# FanControl_1-0.net
KiCad netlist of a schematic drawn in EAGLE
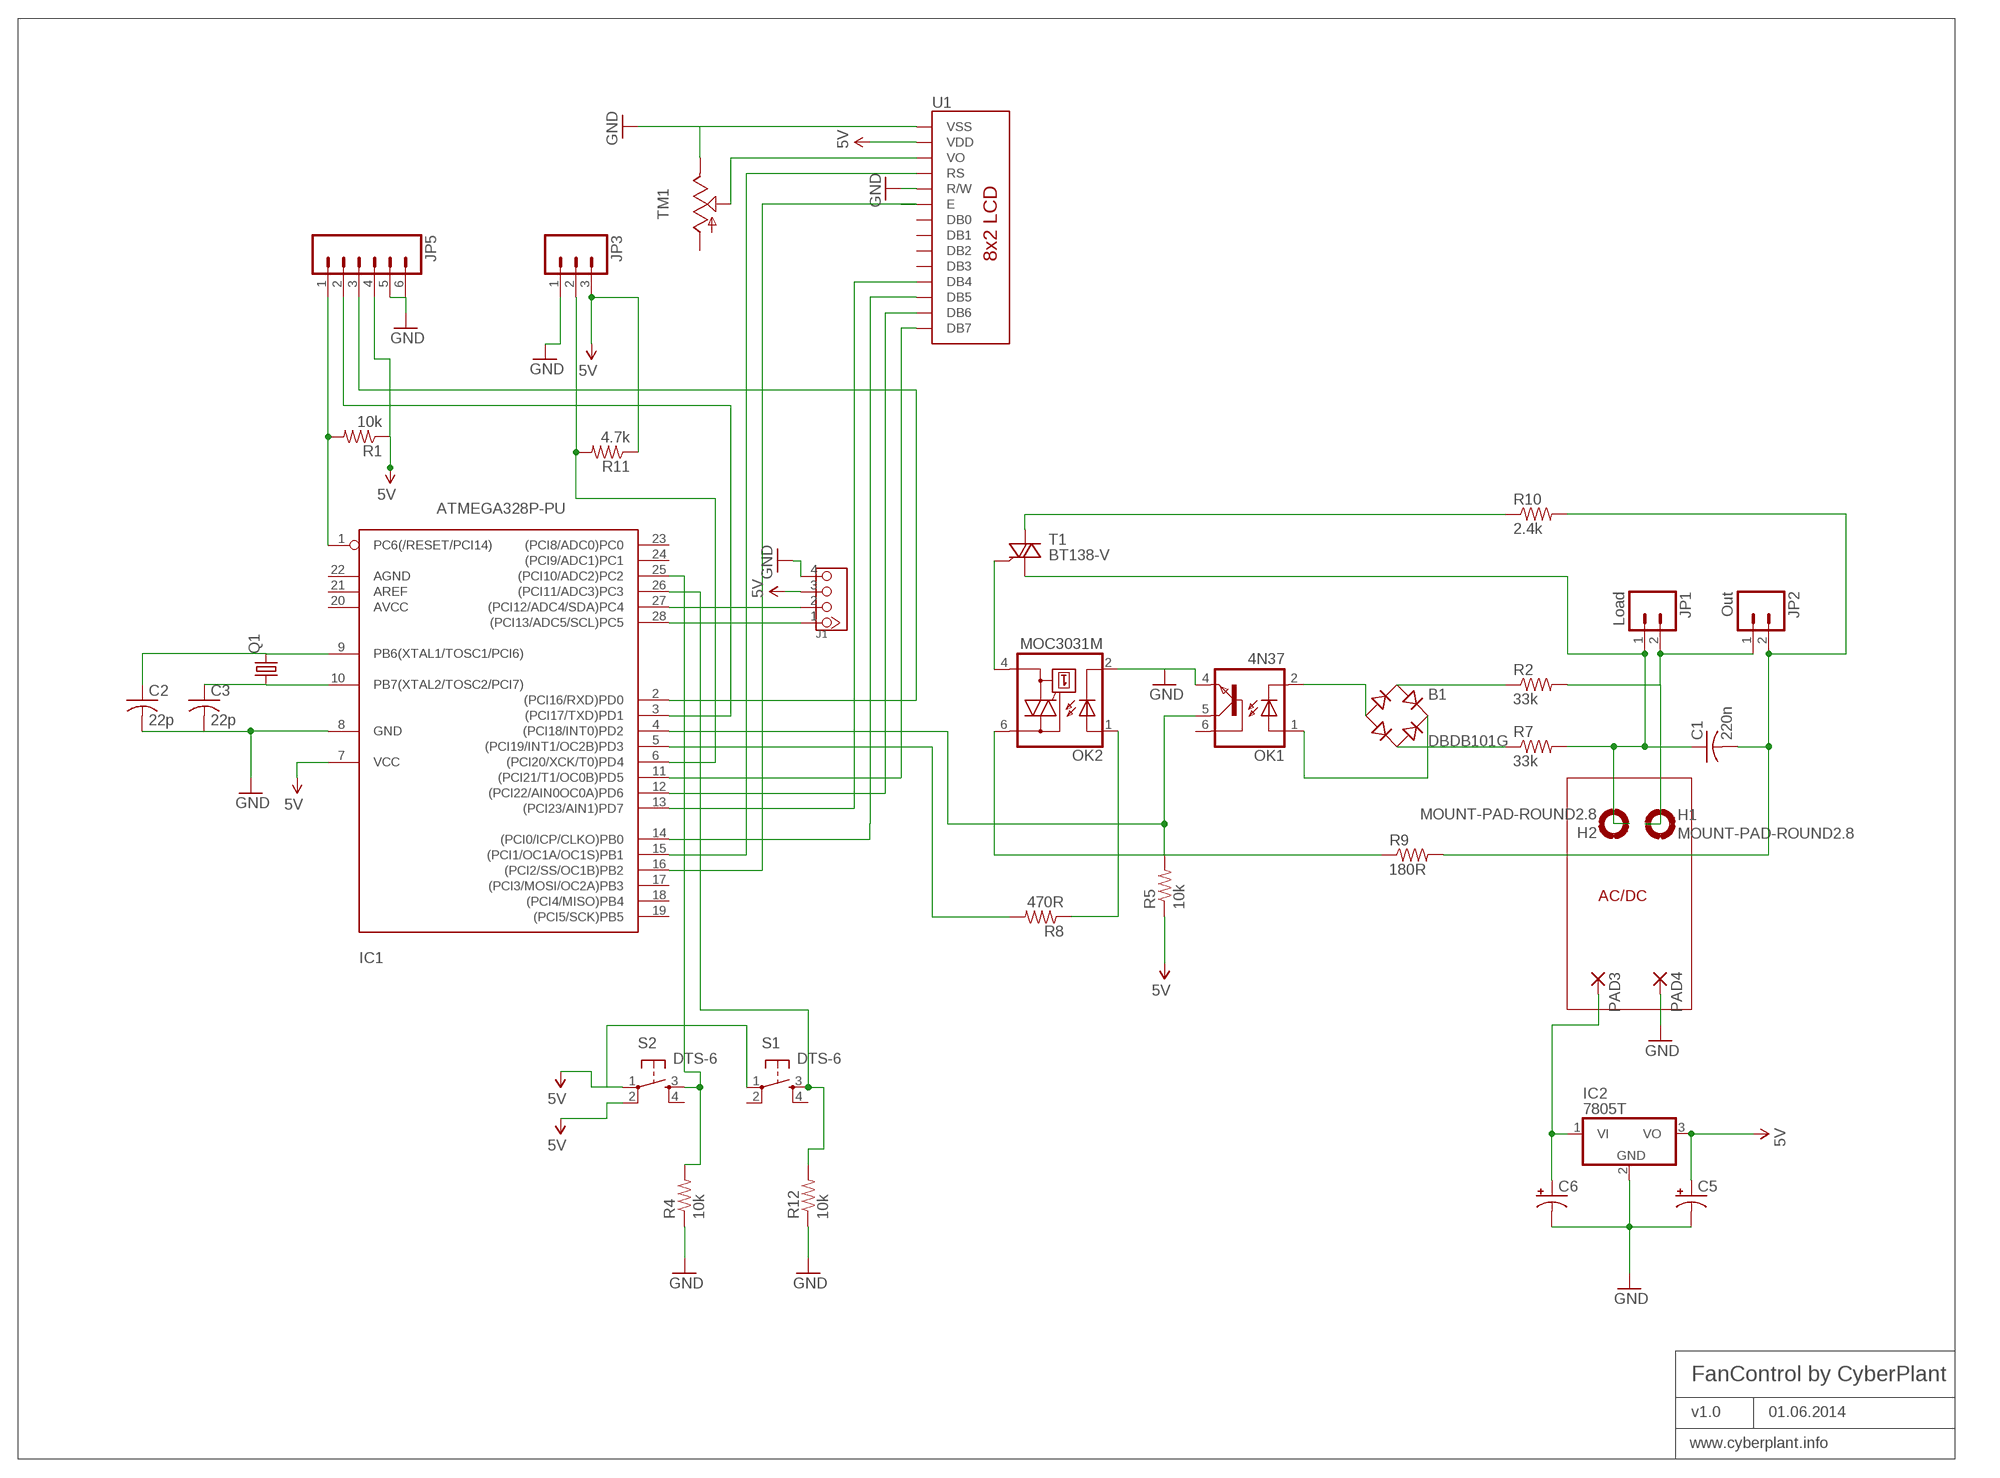
[diagram p0: schematic, sheet 1]

(export (version "E")
  (design (tool "Eeschema 10.0.6"))
  (components
    (comp (ref "B1")
      (value "DBDB101G")
      (footprint "eagle-import:DB")
      (libsource (lib "eagle-import") (part "DB?GDB101"))
    )
    (comp (ref "C1")
      (value "220n")
      (footprint "eagle-import:C150-064X183")
      (libsource (lib "eagle-import") (part "C-US150-064X183"))
    )
    (comp (ref "C2")
      (value "22p")
      (footprint "eagle-import:C050-025X075")
      (libsource (lib "eagle-import") (part "C-US050-025X075"))
    )
    (comp (ref "C3")
      (value "22p")
      (footprint "eagle-import:C050-025X075")
      (libsource (lib "eagle-import") (part "C-US050-025X075"))
    )
    (comp (ref "C5")
      (value "CAP_POLPTH2")
      (footprint "eagle-import:CPOL-RADIAL-10UF-25V")
      (libsource (lib "eagle-import") (part "CAP_POLPTH2"))
    )
    (comp (ref "C6")
      (value "CAP_POLPTH2")
      (footprint "eagle-import:CPOL-RADIAL-10UF-25V")
      (libsource (lib "eagle-import") (part "CAP_POLPTH2"))
    )
    (comp (ref "H1")
      (value "MOUNT-PAD-ROUND2.8")
      (footprint "eagle-import:2,8-PAD")
      (libsource (lib "eagle-import") (part "MOUNT-PAD-ROUND2.8"))
    )
    (comp (ref "H2")
      (value "MOUNT-PAD-ROUND2.8")
      (footprint "eagle-import:2,8-PAD")
      (libsource (lib "eagle-import") (part "MOUNT-PAD-ROUND2.8"))
    )
    (comp (ref "IC1")
      (value "ATMEGA328P-PU")
      (footprint "eagle-import:DIL28-3")
      (libsource (lib "eagle-import") (part "ATMEGA168P-20"))
    )
    (comp (ref "IC2")
      (value "7805T")
      (footprint "eagle-import:TO220H")
      (libsource (lib "eagle-import") (part "78T05"))
    )
    (comp (ref "J1")
      (value "TWIG-4P-2.090D")
      (footprint "eagle-import:4P-2.0-90D")
      (libsource (lib "eagle-import") (part "TWIG-4P-2.090D"))
    )
    (comp (ref "JP1")
      (value "Load")
      (footprint "eagle-import:SCREWTERMINAL-5MM-2")
      (libsource (lib "eagle-import") (part "M025MM"))
    )
    (comp (ref "JP2")
      (value "Out")
      (footprint "eagle-import:SCREWTERMINAL-5MM-2")
      (libsource (lib "eagle-import") (part "M025MM"))
    )
    (comp (ref "JP3")
      (value "M031X03_NO_SILK")
      (footprint "eagle-import:1X03_NO_SILK")
      (libsource (lib "eagle-import") (part "M031X03_NO_SILK"))
    )
    (comp (ref "JP5")
      (value "M06SIP")
      (footprint "eagle-import:1X06")
      (libsource (lib "eagle-import") (part "M06SIP"))
    )
    (comp (ref "OK1")
      (value "4N37")
      (footprint "eagle-import:DIL06")
      (fields (field (name "MF") "FAIRCHILD SEMICONDUCTOR"))
      (libsource (lib "eagle-import") (part "4N37"))
    )
    (comp (ref "OK2")
      (value "MOC3031M")
      (footprint "eagle-import:DIL06")
      (fields (field (name "MF") "FAIRCHILD SEMICONDUCTOR"))
      (libsource (lib "eagle-import") (part "MOC3031M"))
    )
    (comp (ref "PAD3")
      (value "1,6/0,8")
      (footprint "eagle-import:1,6_0,8")
      (libsource (lib "eagle-import") (part "1,6/0,8"))
    )
    (comp (ref "PAD4")
      (value "1,6/0,8")
      (footprint "eagle-import:1,6_0,8")
      (libsource (lib "eagle-import") (part "1,6/0,8"))
    )
    (comp (ref "Q1")
      (value "CRYSTALHC49S")
      (footprint "eagle-import:HC49_S")
      (libsource (lib "eagle-import") (part "CRYSTALHC49S"))
    )
    (comp (ref "R1")
      (value "10k")
      (footprint "eagle-import:1_6W-RES")
      (libsource (lib "eagle-import") (part "RESISTORPTH-1/6W"))
    )
    (comp (ref "R2")
      (value "33k")
      (footprint "eagle-import:AXIAL-0.6")
      (libsource (lib "eagle-import") (part "RESISTORPTH-1W"))
    )
    (comp (ref "R4")
      (value "10k")
      (footprint "eagle-import:1_6W-RES")
      (libsource (lib "eagle-import") (part "RESISTORPTH-1/6W"))
    )
    (comp (ref "R5")
      (value "10k")
      (footprint "eagle-import:1_6W-RES")
      (libsource (lib "eagle-import") (part "RESISTORPTH-1/6W"))
    )
    (comp (ref "R7")
      (value "33k")
      (footprint "eagle-import:AXIAL-0.6")
      (libsource (lib "eagle-import") (part "RESISTORPTH-1W"))
    )
    (comp (ref "R8")
      (value "470R")
      (footprint "eagle-import:AXIAL-0.4")
      (libsource (lib "eagle-import") (part "RESISTORPTH-1/4W"))
    )
    (comp (ref "R9")
      (value "180R")
      (footprint "eagle-import:AXIAL-0.8")
      (libsource (lib "eagle-import") (part "RESISTORPTH-2W"))
    )
    (comp (ref "R10")
      (value "2.4k")
      (footprint "eagle-import:AXIAL-0.8")
      (libsource (lib "eagle-import") (part "RESISTORPTH-2W"))
    )
    (comp (ref "R11")
      (value "4.7k")
      (footprint "eagle-import:AXIAL-0.4")
      (libsource (lib "eagle-import") (part "RESISTORPTH-1/4W"))
    )
    (comp (ref "R12")
      (value "10k")
      (footprint "eagle-import:1_6W-RES")
      (libsource (lib "eagle-import") (part "RESISTORPTH-1/6W"))
    )
    (comp (ref "S1")
      (value "DTS-6")
      (footprint "eagle-import:DTS-6")
      (libsource (lib "eagle-import") (part "DTS-6"))
    )
    (comp (ref "S2")
      (value "DTS-6")
      (footprint "eagle-import:DTS-6")
      (libsource (lib "eagle-import") (part "DTS-6"))
    )
    (comp (ref "T1")
      (value "BT138-V")
      (footprint "eagle-import:TO220BV")
      (libsource (lib "eagle-import") (part "BT138-V"))
    )
    (comp (ref "TM1")
      (value "TRIM")
      (footprint "eagle-import:6MM")
      (libsource (lib "eagle-import") (part "TRIM"))
    )
    (comp (ref "U1")
      (value "LCD-8X2-WH0802A8X2")
      (footprint "eagle-import:LCD-8X2-WH0802A")
      (libsource (lib "eagle-import") (part "LCD-8X2-WH0802A8X2"))
    )
  )
  (nets
    (net (code "1") (name "5V") (class "Default")
      (node (ref "C5") (pin "1") (pinfunction "+_1") (pintype "passive"))
      (node (ref "IC1") (pin "7") (pinfunction "VCC_7") (pintype "bidirectional"))
      (node (ref "IC2") (pin "3") (pinfunction "VO_3") (pintype "passive"))
      (node (ref "J1") (pin "3") (pinfunction "3_3") (pintype "bidirectional"))
      (node (ref "JP3") (pin "3") (pinfunction "3_3") (pintype "passive"))
      (node (ref "JP5") (pin "4") (pinfunction "4_4") (pintype "passive"))
      (node (ref "R1") (pin "1") (pinfunction "1_1") (pintype "passive"))
      (node (ref "R11") (pin "P$1") (pinfunction "1_P$1") (pintype "passive"))
      (node (ref "R5") (pin "1") (pinfunction "1_1") (pintype "passive"))
      (node (ref "S1") (pin "1") (pinfunction "1_1") (pintype "passive"))
      (node (ref "S2") (pin "1") (pinfunction "1_1") (pintype "passive"))
      (node (ref "S2") (pin "2") (pinfunction "2_2") (pintype "passive"))
      (node (ref "U1") (pin "2") (pinfunction "VDD_2") (pintype "power_in"))
    )
    (net (code "2") (name "GND") (class "Default")
      (node (ref "C2") (pin "2") (pinfunction "2_2") (pintype "passive"))
      (node (ref "C3") (pin "2") (pinfunction "2_2") (pintype "passive"))
      (node (ref "C5") (pin "2") (pinfunction "-_2") (pintype "passive"))
      (node (ref "C6") (pin "2") (pinfunction "-_2") (pintype "passive"))
      (node (ref "IC1") (pin "8") (pinfunction "GND_8") (pintype "bidirectional"))
      (node (ref "IC2") (pin "2") (pinfunction "GND_2") (pintype "passive"))
      (node (ref "J1") (pin "4") (pinfunction "4_4") (pintype "bidirectional"))
      (node (ref "JP3") (pin "1") (pinfunction "1_1") (pintype "passive"))
      (node (ref "JP5") (pin "5") (pinfunction "5_5") (pintype "passive"))
      (node (ref "JP5") (pin "6") (pinfunction "6_6") (pintype "passive"))
      (node (ref "OK1") (pin "4") (pinfunction "EMI_4") (pintype "passive"))
      (node (ref "OK2") (pin "2") (pinfunction "C_2") (pintype "passive"))
      (node (ref "PAD4") (pin "1") (pinfunction "P_1") (pintype "passive"))
      (node (ref "R12") (pin "1") (pinfunction "1_1") (pintype "passive"))
      (node (ref "R4") (pin "1") (pinfunction "1_1") (pintype "passive"))
      (node (ref "TM1") (pin "E") (pinfunction "E_E") (pintype "passive"))
      (node (ref "U1") (pin "1") (pinfunction "VSS_1") (pintype "power_in"))
      (node (ref "U1") (pin "5") (pinfunction "R/W_5") (pintype "input"))
    )
    (net (code "3") (name "Net-(C6-+)") (class "Default")
      (node (ref "C6") (pin "1") (pinfunction "+_1") (pintype "passive"))
      (node (ref "IC2") (pin "1") (pinfunction "VI_1") (pintype "input"))
      (node (ref "PAD3") (pin "1") (pinfunction "P_1") (pintype "passive"))
    )
    (net (code "4") (name "Net-(H1-MOUNT)") (class "Default")
      (node (ref "H1") (pin "B2,8") (pinfunction "MOUNT_B2,8") (pintype "passive"))
      (node (ref "JP1") (pin "2") (pinfunction "2_2") (pintype "passive"))
      (node (ref "JP2") (pin "1") (pinfunction "1_1") (pintype "passive"))
      (node (ref "R2") (pin "P$2") (pinfunction "2_P$2") (pintype "passive"))
    )
    (net (code "5") (name "Net-(H2-MOUNT)") (class "Default")
      (node (ref "C1") (pin "1") (pinfunction "1_1") (pintype "passive"))
      (node (ref "H2") (pin "B2,8") (pinfunction "MOUNT_B2,8") (pintype "passive"))
      (node (ref "JP1") (pin "1") (pinfunction "1_1") (pintype "passive"))
      (node (ref "R7") (pin "P$2") (pinfunction "2_P$2") (pintype "passive"))
      (node (ref "T1") (pin "T1") (pinfunction "A1_T1") (pintype "passive"))
    )
    (net (code "6") (name "Net-(IC1-(PCI0{slash}ICP{slash}CLKO)PB0)") (class "Default")
      (node (ref "IC1") (pin "14") (pinfunction "(PCI0/ICP/CLKO)PB0_14") (pintype "bidirectional"))
      (node (ref "U1") (pin "12") (pinfunction "DB5_12") (pintype "bidirectional"))
    )
    (net (code "7") (name "Net-(IC1-(PCI1{slash}OC1A{slash}OC1S)PB1)") (class "Default")
      (node (ref "IC1") (pin "15") (pinfunction "(PCI1/OC1A/OC1S)PB1_15") (pintype "bidirectional"))
      (node (ref "U1") (pin "4") (pinfunction "RS_4") (pintype "input"))
    )
    (net (code "8") (name "Net-(IC1-(PCI2{slash}SS{slash}OC1B)PB2)") (class "Default")
      (node (ref "IC1") (pin "16") (pinfunction "(PCI2/SS/OC1B)PB2_16") (pintype "bidirectional"))
      (node (ref "U1") (pin "6") (pinfunction "E_6") (pintype "input"))
    )
    (net (code "9") (name "Net-(IC1-(PCI10{slash}ADC2)PC2)") (class "Default")
      (node (ref "IC1") (pin "25") (pinfunction "(PCI10/ADC2)PC2_25") (pintype "bidirectional"))
      (node (ref "R4") (pin "2") (pinfunction "2_2") (pintype "passive"))
      (node (ref "S2") (pin "3") (pinfunction "3_3") (pintype "passive"))
    )
    (net (code "10") (name "Net-(IC1-(PCI11{slash}ADC3)PC3)") (class "Default")
      (node (ref "IC1") (pin "26") (pinfunction "(PCI11/ADC3)PC3_26") (pintype "bidirectional"))
      (node (ref "R12") (pin "2") (pinfunction "2_2") (pintype "passive"))
      (node (ref "S1") (pin "3") (pinfunction "3_3") (pintype "passive"))
    )
    (net (code "11") (name "Net-(IC1-(PCI12{slash}ADC4{slash}SDA)PC4)") (class "Default")
      (node (ref "IC1") (pin "27") (pinfunction "(PCI12/ADC4/SDA)PC4_27") (pintype "bidirectional"))
      (node (ref "J1") (pin "2") (pinfunction "2_2") (pintype "bidirectional"))
    )
    (net (code "12") (name "Net-(IC1-(PCI13{slash}ADC5{slash}SCL)PC5)") (class "Default")
      (node (ref "IC1") (pin "28") (pinfunction "(PCI13/ADC5/SCL)PC5_28") (pintype "bidirectional"))
      (node (ref "J1") (pin "1") (pinfunction "1_1") (pintype "bidirectional"))
    )
    (net (code "13") (name "Net-(IC1-(PCI16{slash}RXD)PD0)") (class "Default")
      (node (ref "IC1") (pin "2") (pinfunction "(PCI16/RXD)PD0_2") (pintype "bidirectional"))
      (node (ref "JP5") (pin "3") (pinfunction "3_3") (pintype "passive"))
    )
    (net (code "14") (name "Net-(IC1-(PCI17{slash}TXD)PD1)") (class "Default")
      (node (ref "IC1") (pin "3") (pinfunction "(PCI17/TXD)PD1_3") (pintype "bidirectional"))
      (node (ref "JP5") (pin "2") (pinfunction "2_2") (pintype "passive"))
    )
    (net (code "15") (name "Net-(IC1-(PCI18{slash}INT0)PD2)") (class "Default")
      (node (ref "IC1") (pin "4") (pinfunction "(PCI18/INT0)PD2_4") (pintype "bidirectional"))
      (node (ref "OK1") (pin "5") (pinfunction "COL_5") (pintype "passive"))
      (node (ref "R5") (pin "2") (pinfunction "2_2") (pintype "passive"))
    )
    (net (code "16") (name "Net-(IC1-(PCI19{slash}INT1{slash}OC2B)PD3)") (class "Default")
      (node (ref "IC1") (pin "5") (pinfunction "(PCI19/INT1/OC2B)PD3_5") (pintype "bidirectional"))
      (node (ref "R8") (pin "P$2") (pinfunction "2_P$2") (pintype "passive"))
    )
    (net (code "17") (name "Net-(IC1-(PCI20{slash}XCK{slash}T0)PD4)") (class "Default")
      (node (ref "IC1") (pin "6") (pinfunction "(PCI20/XCK/T0)PD4_6") (pintype "bidirectional"))
      (node (ref "JP3") (pin "2") (pinfunction "2_2") (pintype "passive"))
      (node (ref "R11") (pin "P$2") (pinfunction "2_P$2") (pintype "passive"))
    )
    (net (code "18") (name "Net-(IC1-(PCI21{slash}T1{slash}OC0B)PD5)") (class "Default")
      (node (ref "IC1") (pin "11") (pinfunction "(PCI21/T1/OC0B)PD5_11") (pintype "bidirectional"))
      (node (ref "U1") (pin "14") (pinfunction "DB7_14") (pintype "bidirectional"))
    )
    (net (code "19") (name "Net-(IC1-(PCI22{slash}AIN0OC0A)PD6)") (class "Default")
      (node (ref "IC1") (pin "12") (pinfunction "(PCI22/AIN0OC0A)PD6_12") (pintype "bidirectional"))
      (node (ref "U1") (pin "13") (pinfunction "DB6_13") (pintype "bidirectional"))
    )
    (net (code "20") (name "Net-(IC1-(PCI23{slash}AIN1)PD7)") (class "Default")
      (node (ref "IC1") (pin "13") (pinfunction "(PCI23/AIN1)PD7_13") (pintype "bidirectional"))
      (node (ref "U1") (pin "11") (pinfunction "DB4_11") (pintype "bidirectional"))
    )
    (net (code "21") (name "Net-(IC1-PB6(XTAL1{slash}TOSC1{slash}PCI6))") (class "Default")
      (node (ref "C2") (pin "1") (pinfunction "1_1") (pintype "passive"))
      (node (ref "IC1") (pin "9") (pinfunction "PB6(XTAL1/TOSC1/PCI6)_9") (pintype "bidirectional"))
      (node (ref "Q1") (pin "2") (pinfunction "2_2") (pintype "passive"))
    )
    (net (code "22") (name "Net-(IC1-PB7(XTAL2{slash}TOSC2{slash}PCI7))") (class "Default")
      (node (ref "C3") (pin "1") (pinfunction "1_1") (pintype "passive"))
      (node (ref "IC1") (pin "10") (pinfunction "PB7(XTAL2/TOSC2/PCI7)_10") (pintype "bidirectional"))
      (node (ref "Q1") (pin "1") (pinfunction "1_1") (pintype "passive"))
    )
    (net (code "23") (name "Net-(IC1-PC6({slash}RESET{slash}PCI14))") (class "Default")
      (node (ref "IC1") (pin "1") (pinfunction "PC6(/RESET/PCI14)_1") (pintype "bidirectional"))
      (node (ref "JP5") (pin "1") (pinfunction "1_1") (pintype "passive"))
      (node (ref "R1") (pin "2") (pinfunction "2_2") (pintype "passive"))
    )
    (net (code "24") (name "Net-(OK1-A)") (class "Default")
      (node (ref "B1") (pin "+") (pinfunction "+_+") (pintype "passive"))
      (node (ref "OK1") (pin "1") (pinfunction "A_1") (pintype "passive"))
    )
    (net (code "25") (name "Net-(OK1-C)") (class "Default")
      (node (ref "B1") (pin "-") (pinfunction "-_-") (pintype "passive"))
      (node (ref "OK1") (pin "2") (pinfunction "C_2") (pintype "passive"))
    )
    (net (code "26") (name "Net-(OK2-A)") (class "Default")
      (node (ref "OK2") (pin "1") (pinfunction "A_1") (pintype "passive"))
      (node (ref "R8") (pin "P$1") (pinfunction "1_P$1") (pintype "passive"))
    )
    (net (code "27") (name "Net-(OK2-A1)") (class "Default")
      (node (ref "OK2") (pin "4") (pinfunction "A1_4") (pintype "passive"))
      (node (ref "T1") (pin "G") (pinfunction "G_G") (pintype "passive"))
    )
    (net (code "28") (name "Net-(OK2-A2)") (class "Default")
      (node (ref "OK2") (pin "6") (pinfunction "A2_6") (pintype "passive"))
      (node (ref "R9") (pin "P$1") (pinfunction "1_P$1") (pintype "passive"))
    )
    (net (code "29") (name "Net-(R2-1)") (class "Default")
      (node (ref "B1") (pin "AC1") (pinfunction "AC1_AC1") (pintype "passive"))
      (node (ref "R2") (pin "P$1") (pinfunction "1_P$1") (pintype "passive"))
    )
    (net (code "30") (name "Net-(R7-1)") (class "Default")
      (node (ref "B1") (pin "AC2") (pinfunction "AC2_AC2") (pintype "passive"))
      (node (ref "R7") (pin "P$1") (pinfunction "1_P$1") (pintype "passive"))
    )
    (net (code "31") (name "Net-(R10-1)") (class "Default")
      (node (ref "R10") (pin "P$1") (pinfunction "1_P$1") (pintype "passive"))
      (node (ref "T1") (pin "T2") (pinfunction "A2_T2") (pintype "passive"))
    )
    (net (code "32") (name "Net-(R10-2)") (class "Default")
      (node (ref "C1") (pin "2") (pinfunction "2_2") (pintype "passive"))
      (node (ref "JP2") (pin "2") (pinfunction "2_2") (pintype "passive"))
      (node (ref "R10") (pin "P$2") (pinfunction "2_P$2") (pintype "passive"))
      (node (ref "R9") (pin "P$2") (pinfunction "2_P$2") (pintype "passive"))
    )
    (net (code "33") (name "Net-(U1-VO)") (class "Default")
      (node (ref "TM1") (pin "S") (pinfunction "S_S") (pintype "passive"))
      (node (ref "U1") (pin "3") (pinfunction "VO_3") (pintype "bidirectional"))
    )
    (net (code "34") (name "unconnected-(IC1-(PCI3{slash}MOSI{slash}OC2A)PB3-Pad17)") (class "Default")
      (node (ref "IC1") (pin "17") (pinfunction "(PCI3/MOSI/OC2A)PB3_17") (pintype "bidirectional"))
    )
    (net (code "35") (name "unconnected-(IC1-(PCI4{slash}MISO)PB4-Pad18)") (class "Default")
      (node (ref "IC1") (pin "18") (pinfunction "(PCI4/MISO)PB4_18") (pintype "bidirectional"))
    )
    (net (code "36") (name "unconnected-(IC1-(PCI5{slash}SCK)PB5-Pad19)") (class "Default")
      (node (ref "IC1") (pin "19") (pinfunction "(PCI5/SCK)PB5_19") (pintype "bidirectional"))
    )
    (net (code "37") (name "unconnected-(IC1-(PCI8{slash}ADC0)PC0-Pad23)") (class "Default")
      (node (ref "IC1") (pin "23") (pinfunction "(PCI8/ADC0)PC0_23") (pintype "bidirectional"))
    )
    (net (code "38") (name "unconnected-(IC1-(PCI9{slash}ADC1)PC1-Pad24)") (class "Default")
      (node (ref "IC1") (pin "24") (pinfunction "(PCI9/ADC1)PC1_24") (pintype "bidirectional"))
    )
    (net (code "39") (name "unconnected-(IC1-AGND-Pad22)") (class "Default")
      (node (ref "IC1") (pin "22") (pinfunction "AGND_22") (pintype "bidirectional"))
    )
    (net (code "40") (name "unconnected-(IC1-AREF-Pad21)") (class "Default")
      (node (ref "IC1") (pin "21") (pinfunction "AREF_21") (pintype "bidirectional"))
    )
    (net (code "41") (name "unconnected-(IC1-AVCC-Pad20)") (class "Default")
      (node (ref "IC1") (pin "20") (pinfunction "AVCC_20") (pintype "bidirectional"))
    )
    (net (code "42") (name "unconnected-(OK1-BAS-Pad6)") (class "Default")
      (node (ref "OK1") (pin "6") (pinfunction "BAS_6") (pintype "passive"))
    )
    (net (code "43") (name "unconnected-(S1-Pad2)") (class "Default")
      (node (ref "S1") (pin "2") (pinfunction "2_2") (pintype "passive"))
    )
    (net (code "44") (name "unconnected-(S1-Pad4)") (class "Default")
      (node (ref "S1") (pin "4") (pinfunction "4_4") (pintype "passive"))
    )
    (net (code "45") (name "unconnected-(S2-Pad4)") (class "Default")
      (node (ref "S2") (pin "4") (pinfunction "4_4") (pintype "passive"))
    )
    (net (code "46") (name "unconnected-(TM1-PadA)") (class "Default")
      (node (ref "TM1") (pin "A") (pinfunction "A_A") (pintype "passive"))
    )
    (net (code "47") (name "unconnected-(U1-DB0-Pad7)") (class "Default")
      (node (ref "U1") (pin "7") (pinfunction "DB0_7") (pintype "bidirectional"))
    )
    (net (code "48") (name "unconnected-(U1-DB1-Pad8)") (class "Default")
      (node (ref "U1") (pin "8") (pinfunction "DB1_8") (pintype "bidirectional"))
    )
    (net (code "49") (name "unconnected-(U1-DB2-Pad9)") (class "Default")
      (node (ref "U1") (pin "9") (pinfunction "DB2_9") (pintype "bidirectional"))
    )
    (net (code "50") (name "unconnected-(U1-DB3-Pad10)") (class "Default")
      (node (ref "U1") (pin "10") (pinfunction "DB3_10") (pintype "bidirectional"))
    )
  )
)
